# FidoBark.net
KiCad netlist of a schematic drawn in EAGLE
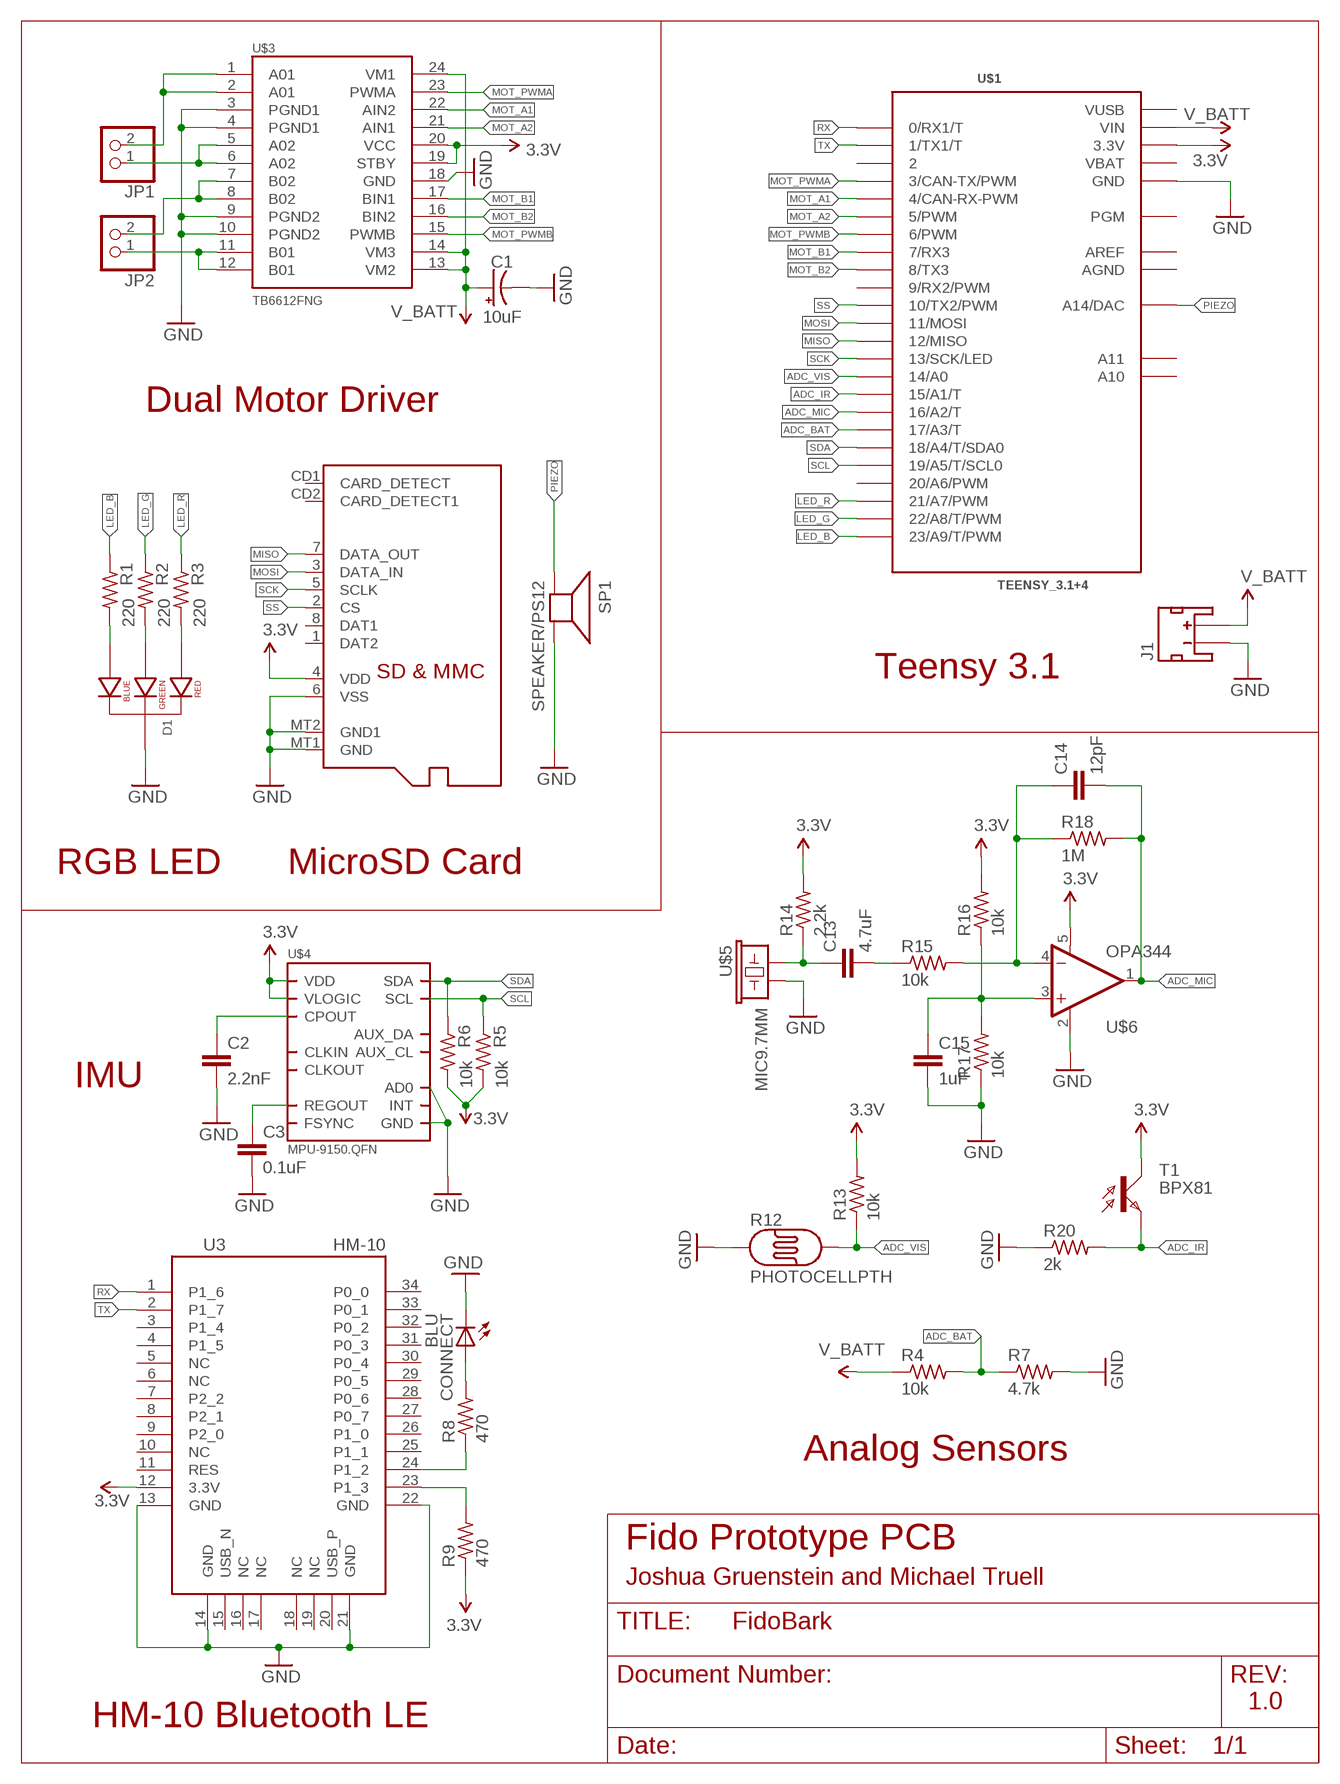
[diagram p0: schematic, sheet 1]

(export (version "E")
  (design (tool "Eeschema 10.0.6"))
  (components
    (comp (ref "C1")
      (value "10uF")
      (footprint "eagle-import:EIA3216")
      (libsource (lib "eagle-import") (part "CAP_POL1206"))
    )
    (comp (ref "C2")
      (value "2.2nF")
      (footprint "eagle-import:C0603")
      (libsource (lib "eagle-import") (part "C-EUC0603"))
    )
    (comp (ref "C3")
      (value "0.1uF")
      (footprint "eagle-import:C0603")
      (libsource (lib "eagle-import") (part "C-EUC0603"))
    )
    (comp (ref "C13")
      (value "4.7uF")
      (footprint "eagle-import:0603-CAP")
      (libsource (lib "eagle-import") (part "CAP0603-CAP"))
    )
    (comp (ref "C14")
      (value "12pF")
      (footprint "eagle-import:0603-CAP")
      (libsource (lib "eagle-import") (part "CAP0603-CAP"))
    )
    (comp (ref "C15")
      (value "1uF")
      (footprint "eagle-import:0603-CAP")
      (libsource (lib "eagle-import") (part "CAP0603-CAP"))
    )
    (comp (ref "CONNECT")
      (value "BLU")
      (footprint "eagle-import:CHIPLED_0805")
      (libsource (lib "eagle-import") (part "LEDCHIPLED_0805"))
    )
    (comp (ref "D1")
      (value "LED-RGB-CC-THRUCLEAR")
      (footprint "eagle-import:LED-RGB-THRU")
      (libsource (lib "eagle-import") (part "LED-RGB-CC-THRUCLEAR"))
    )
    (comp (ref "J1")
      (value "JST_2MM_MALE")
      (footprint "eagle-import:JST-2-SMD")
      (libsource (lib "eagle-import") (part "JST_2MM_MALE"))
    )
    (comp (ref "JP1")
      (value "PINHD-1X2")
      (footprint "eagle-import:1X02")
      (libsource (lib "eagle-import") (part "PINHD-1X2"))
    )
    (comp (ref "JP2")
      (value "PINHD-1X2")
      (footprint "eagle-import:1X02")
      (libsource (lib "eagle-import") (part "PINHD-1X2"))
    )
    (comp (ref "R1")
      (value "220")
      (footprint "eagle-import:R0603")
      (libsource (lib "eagle-import") (part "rcl_R-US_R0603"))
    )
    (comp (ref "R2")
      (value "220")
      (footprint "eagle-import:R0603")
      (libsource (lib "eagle-import") (part "rcl_R-US_R0603"))
    )
    (comp (ref "R3")
      (value "220")
      (footprint "eagle-import:R0603")
      (libsource (lib "eagle-import") (part "rcl_R-US_R0603"))
    )
    (comp (ref "R4")
      (value "10k")
      (footprint "eagle-import:R0603")
      (libsource (lib "eagle-import") (part "rcl_R-US_R0603"))
    )
    (comp (ref "R5")
      (value "10k")
      (footprint "eagle-import:R0603")
      (libsource (lib "eagle-import") (part "rcl_R-US_R0603"))
    )
    (comp (ref "R6")
      (value "10k")
      (footprint "eagle-import:R0603")
      (libsource (lib "eagle-import") (part "rcl_R-US_R0603"))
    )
    (comp (ref "R7")
      (value "4.7k")
      (footprint "eagle-import:R0603")
      (libsource (lib "eagle-import") (part "rcl_R-US_R0603"))
    )
    (comp (ref "R8")
      (value "470")
      (footprint "eagle-import:R0603")
      (libsource (lib "eagle-import") (part "R-US_R0603"))
    )
    (comp (ref "R9")
      (value "470")
      (footprint "eagle-import:R0603")
      (libsource (lib "eagle-import") (part "R-US_R0603"))
    )
    (comp (ref "R12")
      (value "PHOTOCELLPTH")
      (footprint "eagle-import:PHOTOCELL")
      (libsource (lib "eagle-import") (part "PHOTOCELLPTH"))
    )
    (comp (ref "R13")
      (value "10k")
      (footprint "eagle-import:R0603")
      (libsource (lib "eagle-import") (part "R-US_R0603"))
    )
    (comp (ref "R14")
      (value "2.2k")
      (footprint "eagle-import:R0603")
      (libsource (lib "eagle-import") (part "R-US_R0603"))
    )
    (comp (ref "R15")
      (value "10k")
      (footprint "eagle-import:R0603")
      (libsource (lib "eagle-import") (part "R-US_R0603"))
    )
    (comp (ref "R16")
      (value "10k")
      (footprint "eagle-import:R0603")
      (libsource (lib "eagle-import") (part "R-US_R0603"))
    )
    (comp (ref "R17")
      (value "10k")
      (footprint "eagle-import:R0603")
      (libsource (lib "eagle-import") (part "R-US_R0603"))
    )
    (comp (ref "R18")
      (value "1M")
      (footprint "eagle-import:R0603")
      (libsource (lib "eagle-import") (part "R-US_R0603"))
    )
    (comp (ref "R20")
      (value "2k")
      (footprint "eagle-import:R0603")
      (libsource (lib "eagle-import") (part "R-US_R0603"))
    )
    (comp (ref "SP1")
      (value "SPEAKER/PS12")
      (footprint "eagle-import:PS12")
      (libsource (lib "eagle-import") (part "SPEAKER/PS12"))
    )
    (comp (ref "T1")
      (value "BPX81")
      (footprint "eagle-import:BPX81")
      (libsource (lib "eagle-import") (part "BPX81"))
    )
    (comp (ref "U$1")
      (value "TEENSY_3.1+4")
      (footprint "eagle-import:TEENSY_3.1+4")
      (libsource (lib "eagle-import") (part "TEENSY_3.1+4"))
    )
    (comp (ref "U$2")
      (value "MICROSD")
      (footprint "eagle-import:MICROSD")
      (libsource (lib "eagle-import") (part "MICROSD"))
    )
    (comp (ref "U$3")
      (value "TB6612FNG")
      (footprint "eagle-import:SSOP24")
      (libsource (lib "eagle-import") (part "TB6612FNG"))
    )
    (comp (ref "U$4")
      (value "MPU-9150.QFN")
      (footprint "eagle-import:QFN.24.4X4")
      (libsource (lib "eagle-import") (part "MPU-9150.QFN"))
    )
    (comp (ref "U$5")
      (value "MIC9.7MM")
      (footprint "eagle-import:MIC-9.7MM")
      (libsource (lib "eagle-import") (part "MIC9.7MM"))
    )
    (comp (ref "U$6")
      (value "OPA344")
      (footprint "eagle-import:SOT23-5")
      (libsource (lib "eagle-import") (part "OPA344"))
    )
    (comp (ref "U3")
      (value "HM-10")
      (footprint "eagle-import:HM-10")
      (libsource (lib "eagle-import") (part "HM-10"))
    )
  )
  (nets
    (net (code "1") (name "/AGND") (class "Default")
      (node (ref "U$1") (pin "AGND") (pinfunction "AGND_AGND") (pintype "power_in"))
    )
    (net (code "2") (name "/AREF") (class "Default")
      (node (ref "U$1") (pin "AREF") (pinfunction "AREF_AREF") (pintype "power_in"))
    )
    (net (code "3") (name "/VBAT") (class "Default")
      (node (ref "U$1") (pin "VBAT") (pinfunction "VBAT_VBAT") (pintype "power_in"))
    )
    (net (code "4") (name "/VUSB") (class "Default")
      (node (ref "U$1") (pin "VUSB") (pinfunction "VUSB_VUSB") (pintype "power_in"))
    )
    (net (code "5") (name "3.3V") (class "Default")
      (node (ref "R13") (pin "2") (pinfunction "2_2") (pintype "passive"))
      (node (ref "R14") (pin "2") (pinfunction "2_2") (pintype "passive"))
      (node (ref "R16") (pin "2") (pinfunction "2_2") (pintype "passive"))
      (node (ref "R5") (pin "2") (pinfunction "2_2") (pintype "passive"))
      (node (ref "R6") (pin "2") (pinfunction "2_2") (pintype "passive"))
      (node (ref "R9") (pin "1") (pinfunction "1_1") (pintype "passive"))
      (node (ref "T1") (pin "C") (pinfunction "C_C") (pintype "passive"))
      (node (ref "U$1") (pin "3.3V") (pinfunction "3.3V_3.3V") (pintype "power_in"))
      (node (ref "U$1") (pin "3.3V1") (pinfunction "3.3V_3.3V1") (pintype "power_in"))
      (node (ref "U$2") (pin "4") (pinfunction "VDD_4") (pintype "power_in"))
      (node (ref "U$3") (pin "19") (pinfunction "STBY_19") (pintype "bidirectional"))
      (node (ref "U$3") (pin "20") (pinfunction "VCC_20") (pintype "bidirectional"))
      (node (ref "U$4") (pin "13") (pinfunction "VDD_13") (pintype "bidirectional"))
      (node (ref "U$4") (pin "3") (pinfunction "VDD_3") (pintype "bidirectional"))
      (node (ref "U$4") (pin "8") (pinfunction "VLOGIC_8") (pintype "bidirectional"))
      (node (ref "U$6") (pin "5") (pinfunction "V+_5") (pintype "power_in"))
      (node (ref "U3") (pin "12") (pinfunction "3.3V_12") (pintype "bidirectional"))
    )
    (net (code "6") (name "ADC_BAT") (class "Default")
      (node (ref "R4") (pin "2") (pinfunction "2_2") (pintype "passive"))
      (node (ref "R7") (pin "1") (pinfunction "1_1") (pintype "passive"))
      (node (ref "U$1") (pin "17/A3") (pinfunction "17/A3/T_17/A3") (pintype "bidirectional"))
    )
    (net (code "7") (name "ADC_IR") (class "Default")
      (node (ref "R20") (pin "2") (pinfunction "2_2") (pintype "passive"))
      (node (ref "T1") (pin "E") (pinfunction "E_E") (pintype "passive"))
      (node (ref "U$1") (pin "15/A1") (pinfunction "15/A1/T_15/A1") (pintype "bidirectional"))
    )
    (net (code "8") (name "ADC_MIC") (class "Default")
      (node (ref "C14") (pin "2") (pinfunction "2_2") (pintype "passive"))
      (node (ref "R18") (pin "2") (pinfunction "2_2") (pintype "passive"))
      (node (ref "U$1") (pin "16/A2") (pinfunction "16/A2/T_16/A2") (pintype "bidirectional"))
      (node (ref "U$6") (pin "1") (pinfunction "OUT_1") (pintype "output"))
    )
    (net (code "9") (name "ADC_VIS") (class "Default")
      (node (ref "R12") (pin "2") (pinfunction "P$2_2") (pintype "bidirectional"))
      (node (ref "R13") (pin "1") (pinfunction "1_1") (pintype "passive"))
      (node (ref "U$1") (pin "14/A0") (pinfunction "14/A0_14/A0") (pintype "bidirectional"))
    )
    (net (code "10") (name "GND") (class "Default")
      (node (ref "C1") (pin "C") (pinfunction "-_C") (pintype "passive"))
      (node (ref "C15") (pin "2") (pinfunction "2_2") (pintype "passive"))
      (node (ref "C2") (pin "2") (pinfunction "2_2") (pintype "passive"))
      (node (ref "C3") (pin "2") (pinfunction "2_2") (pintype "passive"))
      (node (ref "CONNECT") (pin "C") (pinfunction "C_C") (pintype "passive"))
      (node (ref "D1") (pin "2") (pinfunction "CATHODE_2") (pintype "bidirectional"))
      (node (ref "J1") (pin "1") (pinfunction "-_1") (pintype "bidirectional"))
      (node (ref "R12") (pin "1") (pinfunction "P$1_1") (pintype "bidirectional"))
      (node (ref "R17") (pin "1") (pinfunction "1_1") (pintype "passive"))
      (node (ref "R20") (pin "1") (pinfunction "1_1") (pintype "passive"))
      (node (ref "R7") (pin "2") (pinfunction "2_2") (pintype "passive"))
      (node (ref "SP1") (pin "P$2") (pinfunction "-_P$2") (pintype "passive"))
      (node (ref "U$1") (pin "GND") (pinfunction "GND_GND") (pintype "power_in"))
      (node (ref "U$1") (pin "GND1") (pinfunction "GND_GND1") (pintype "power_in"))
      (node (ref "U$2") (pin "6") (pinfunction "VSS_6") (pintype "power_in"))
      (node (ref "U$2") (pin "MT1") (pinfunction "GND_MT1") (pintype "power_in"))
      (node (ref "U$2") (pin "MT2") (pinfunction "GND1_MT2") (pintype "power_in"))
      (node (ref "U$3") (pin "10") (pinfunction "PGND2_10") (pintype "bidirectional"))
      (node (ref "U$3") (pin "18") (pinfunction "GND_18") (pintype "bidirectional"))
      (node (ref "U$3") (pin "3") (pinfunction "PGND1_3") (pintype "bidirectional"))
      (node (ref "U$3") (pin "4") (pinfunction "PGND1_4") (pintype "bidirectional"))
      (node (ref "U$3") (pin "9") (pinfunction "PGND2_9") (pintype "bidirectional"))
      (node (ref "U$4") (pin "15") (pinfunction "GND_15") (pintype "bidirectional"))
      (node (ref "U$4") (pin "17") (pinfunction "GND_17") (pintype "bidirectional"))
      (node (ref "U$4") (pin "18") (pinfunction "GND_18") (pintype "bidirectional"))
      (node (ref "U$4") (pin "9") (pinfunction "AD0_9") (pintype "bidirectional"))
      (node (ref "U$5") (pin "2") (pinfunction "2_2") (pintype "passive"))
      (node (ref "U$6") (pin "2") (pinfunction "V-_2") (pintype "power_in"))
      (node (ref "U3") (pin "13") (pinfunction "GND_13") (pintype "bidirectional"))
      (node (ref "U3") (pin "14") (pinfunction "GND_14") (pintype "bidirectional"))
      (node (ref "U3") (pin "21") (pinfunction "GND_21") (pintype "bidirectional"))
      (node (ref "U3") (pin "22") (pinfunction "GND_22") (pintype "bidirectional"))
    )
    (net (code "11") (name "LED_B") (class "Default")
      (node (ref "R1") (pin "1") (pinfunction "1_1") (pintype "passive"))
      (node (ref "U$1") (pin "23/A9") (pinfunction "23/A9/T/PWM_23/A9") (pintype "bidirectional"))
    )
    (net (code "12") (name "LED_G") (class "Default")
      (node (ref "R2") (pin "1") (pinfunction "1_1") (pintype "passive"))
      (node (ref "U$1") (pin "22/A8") (pinfunction "22/A8/T/PWM_22/A8") (pintype "bidirectional"))
    )
    (net (code "13") (name "LED_R") (class "Default")
      (node (ref "R3") (pin "1") (pinfunction "1_1") (pintype "passive"))
      (node (ref "U$1") (pin "21/A7") (pinfunction "21/A7/PWM_21/A7") (pintype "bidirectional"))
    )
    (net (code "14") (name "MISO") (class "Default")
      (node (ref "U$1") (pin "12") (pinfunction "12/MISO_12") (pintype "bidirectional"))
      (node (ref "U$2") (pin "7") (pinfunction "DATA_OUT_7") (pintype "output"))
    )
    (net (code "15") (name "MOSI") (class "Default")
      (node (ref "U$1") (pin "11") (pinfunction "11/MOSI_11") (pintype "bidirectional"))
      (node (ref "U$2") (pin "3") (pinfunction "DATA_IN_3") (pintype "input"))
    )
    (net (code "16") (name "MOT_A1") (class "Default")
      (node (ref "U$1") (pin "4") (pinfunction "4/CAN-RX-PWM_4") (pintype "bidirectional"))
      (node (ref "U$3") (pin "22") (pinfunction "AIN2_22") (pintype "bidirectional"))
    )
    (net (code "17") (name "MOT_A2") (class "Default")
      (node (ref "U$1") (pin "5") (pinfunction "5/PWM_5") (pintype "bidirectional"))
      (node (ref "U$3") (pin "21") (pinfunction "AIN1_21") (pintype "bidirectional"))
    )
    (net (code "18") (name "MOT_B1") (class "Default")
      (node (ref "U$1") (pin "7") (pinfunction "7/RX3_7") (pintype "bidirectional"))
      (node (ref "U$3") (pin "17") (pinfunction "BIN1_17") (pintype "bidirectional"))
    )
    (net (code "19") (name "MOT_B2") (class "Default")
      (node (ref "U$1") (pin "8") (pinfunction "8/TX3_8") (pintype "bidirectional"))
      (node (ref "U$3") (pin "16") (pinfunction "BIN2_16") (pintype "bidirectional"))
    )
    (net (code "20") (name "MOT_PWMA") (class "Default")
      (node (ref "U$1") (pin "3") (pinfunction "3/CAN-TX/PWM_3") (pintype "bidirectional"))
      (node (ref "U$3") (pin "23") (pinfunction "PWMA_23") (pintype "bidirectional"))
    )
    (net (code "21") (name "MOT_PWMB") (class "Default")
      (node (ref "U$1") (pin "6") (pinfunction "6/PWM_6") (pintype "bidirectional"))
      (node (ref "U$3") (pin "15") (pinfunction "PWMB_15") (pintype "bidirectional"))
    )
    (net (code "22") (name "Net-(C13-Pad1)") (class "Default")
      (node (ref "C13") (pin "1") (pinfunction "1_1") (pintype "passive"))
      (node (ref "R14") (pin "1") (pinfunction "1_1") (pintype "passive"))
      (node (ref "U$5") (pin "1") (pinfunction "1_1") (pintype "passive"))
    )
    (net (code "23") (name "Net-(C13-Pad2)") (class "Default")
      (node (ref "C13") (pin "2") (pinfunction "2_2") (pintype "passive"))
      (node (ref "R15") (pin "1") (pinfunction "1_1") (pintype "passive"))
    )
    (net (code "24") (name "Net-(CONNECT-PadA)") (class "Default")
      (node (ref "CONNECT") (pin "A") (pinfunction "A_A") (pintype "passive"))
      (node (ref "R8") (pin "2") (pinfunction "2_2") (pintype "passive"))
    )
    (net (code "25") (name "Net-(D1-BLUE_CATHODE)") (class "Default")
      (node (ref "D1") (pin "4") (pinfunction "BLUE_CATHODE_4") (pintype "bidirectional"))
      (node (ref "R1") (pin "2") (pinfunction "2_2") (pintype "passive"))
    )
    (net (code "26") (name "Net-(D1-GREEN_CATHODE)") (class "Default")
      (node (ref "D1") (pin "3") (pinfunction "GREEN_CATHODE_3") (pintype "bidirectional"))
      (node (ref "R2") (pin "2") (pinfunction "2_2") (pintype "passive"))
    )
    (net (code "27") (name "Net-(D1-RED_CATHODE)") (class "Default")
      (node (ref "D1") (pin "1") (pinfunction "RED_CATHODE_1") (pintype "bidirectional"))
      (node (ref "R3") (pin "2") (pinfunction "2_2") (pintype "passive"))
    )
    (net (code "28") (name "Net-(JP1-Pad1)") (class "Default")
      (node (ref "JP1") (pin "1") (pinfunction "1_1") (pintype "passive"))
      (node (ref "U$3") (pin "5") (pinfunction "A02_5") (pintype "bidirectional"))
      (node (ref "U$3") (pin "6") (pinfunction "A02_6") (pintype "bidirectional"))
    )
    (net (code "29") (name "Net-(JP1-Pad2)") (class "Default")
      (node (ref "JP1") (pin "2") (pinfunction "2_2") (pintype "passive"))
      (node (ref "U$3") (pin "1") (pinfunction "A01_1") (pintype "bidirectional"))
      (node (ref "U$3") (pin "2") (pinfunction "A01_2") (pintype "bidirectional"))
    )
    (net (code "30") (name "Net-(JP2-Pad1)") (class "Default")
      (node (ref "JP2") (pin "1") (pinfunction "1_1") (pintype "passive"))
      (node (ref "U$3") (pin "11") (pinfunction "B01_11") (pintype "bidirectional"))
      (node (ref "U$3") (pin "12") (pinfunction "B01_12") (pintype "bidirectional"))
    )
    (net (code "31") (name "Net-(JP2-Pad2)") (class "Default")
      (node (ref "JP2") (pin "2") (pinfunction "2_2") (pintype "passive"))
      (node (ref "U$3") (pin "7") (pinfunction "B02_7") (pintype "bidirectional"))
      (node (ref "U$3") (pin "8") (pinfunction "B02_8") (pintype "bidirectional"))
    )
    (net (code "32") (name "Net-(U$4-CPOUT)") (class "Default")
      (node (ref "C2") (pin "1") (pinfunction "1_1") (pintype "passive"))
      (node (ref "U$4") (pin "20") (pinfunction "CPOUT_20") (pintype "bidirectional"))
    )
    (net (code "33") (name "Net-(U$4-REGOUT)") (class "Default")
      (node (ref "C3") (pin "1") (pinfunction "1_1") (pintype "passive"))
      (node (ref "U$4") (pin "10") (pinfunction "REGOUT_10") (pintype "bidirectional"))
    )
    (net (code "34") (name "Net-(U$6-+IN)") (class "Default")
      (node (ref "C15") (pin "1") (pinfunction "1_1") (pintype "passive"))
      (node (ref "R16") (pin "1") (pinfunction "1_1") (pintype "passive"))
      (node (ref "R17") (pin "2") (pinfunction "2_2") (pintype "passive"))
      (node (ref "U$6") (pin "3") (pinfunction "+IN_3") (pintype "input"))
    )
    (net (code "35") (name "Net-(U$6--IN)") (class "Default")
      (node (ref "C14") (pin "1") (pinfunction "1_1") (pintype "passive"))
      (node (ref "R15") (pin "2") (pinfunction "2_2") (pintype "passive"))
      (node (ref "R18") (pin "1") (pinfunction "1_1") (pintype "passive"))
      (node (ref "U$6") (pin "4") (pinfunction "-IN_4") (pintype "input"))
    )
    (net (code "36") (name "Net-(U3-P1_2)") (class "Default")
      (node (ref "R8") (pin "1") (pinfunction "1_1") (pintype "passive"))
      (node (ref "U3") (pin "24") (pinfunction "P1_2_24") (pintype "bidirectional"))
    )
    (net (code "37") (name "Net-(U3-P1_3)") (class "Default")
      (node (ref "R9") (pin "2") (pinfunction "2_2") (pintype "passive"))
      (node (ref "U3") (pin "23") (pinfunction "P1_3_23") (pintype "bidirectional"))
    )
    (net (code "38") (name "PIEZO") (class "Default")
      (node (ref "SP1") (pin "P$1") (pinfunction "+_P$1") (pintype "passive"))
      (node (ref "U$1") (pin "A14") (pinfunction "A14/DAC_A14") (pintype "bidirectional"))
    )
    (net (code "39") (name "RX") (class "Default")
      (node (ref "U$1") (pin "0") (pinfunction "0/RX1/T_0") (pintype "bidirectional"))
      (node (ref "U3") (pin "1") (pinfunction "P1_6_1") (pintype "bidirectional"))
    )
    (net (code "40") (name "SCK") (class "Default")
      (node (ref "U$1") (pin "13") (pinfunction "13/SCK/LED_13") (pintype "bidirectional"))
      (node (ref "U$2") (pin "5") (pinfunction "SCLK_5") (pintype "input"))
    )
    (net (code "41") (name "SCL") (class "Default")
      (node (ref "R5") (pin "1") (pinfunction "1_1") (pintype "passive"))
      (node (ref "U$1") (pin "19/A5") (pinfunction "19/A5/T/SCL0_19/A5") (pintype "bidirectional"))
      (node (ref "U$4") (pin "23") (pinfunction "SCL_23") (pintype "bidirectional"))
    )
    (net (code "42") (name "SDA") (class "Default")
      (node (ref "R6") (pin "1") (pinfunction "1_1") (pintype "passive"))
      (node (ref "U$1") (pin "18/A4") (pinfunction "18/A4/T/SDA0_18/A4") (pintype "bidirectional"))
      (node (ref "U$4") (pin "24") (pinfunction "SDA_24") (pintype "bidirectional"))
    )
    (net (code "43") (name "SS") (class "Default")
      (node (ref "U$1") (pin "10") (pinfunction "10/TX2/PWM_10") (pintype "bidirectional"))
      (node (ref "U$2") (pin "2") (pinfunction "CS_2") (pintype "input"))
    )
    (net (code "44") (name "TX") (class "Default")
      (node (ref "U$1") (pin "1") (pinfunction "1/TX1/T_1") (pintype "bidirectional"))
      (node (ref "U3") (pin "2") (pinfunction "P1_7_2") (pintype "bidirectional"))
    )
    (net (code "45") (name "V_BATT") (class "Default")
      (node (ref "C1") (pin "A") (pinfunction "+_A") (pintype "passive"))
      (node (ref "J1") (pin "2") (pinfunction "+_2") (pintype "bidirectional"))
      (node (ref "R4") (pin "1") (pinfunction "1_1") (pintype "passive"))
      (node (ref "U$1") (pin "VIN") (pinfunction "VIN_VIN") (pintype "power_in"))
      (node (ref "U$3") (pin "13") (pinfunction "VM2_13") (pintype "bidirectional"))
      (node (ref "U$3") (pin "14") (pinfunction "VM3_14") (pintype "bidirectional"))
      (node (ref "U$3") (pin "24") (pinfunction "VM1_24") (pintype "bidirectional"))
    )
    (net (code "46") (name "unconnected-(J1-PAD1-PadNC1)") (class "Default")
      (node (ref "J1") (pin "NC1") (pinfunction "PAD1_NC1") (pintype "bidirectional"))
    )
    (net (code "47") (name "unconnected-(J1-PAD2-PadNC2)") (class "Default")
      (node (ref "J1") (pin "NC2") (pinfunction "PAD2_NC2") (pintype "bidirectional"))
    )
    (net (code "48") (name "unconnected-(U$1-9{slash}RX2{slash}PWM-Pad9)") (class "Default")
      (node (ref "U$1") (pin "9") (pinfunction "9/RX2/PWM_9") (pintype "bidirectional"))
    )
    (net (code "49") (name "unconnected-(U$1-20{slash}A6{slash}PWM-Pad20{slash}A6)") (class "Default")
      (node (ref "U$1") (pin "20/A6") (pinfunction "20/A6/PWM_20/A6") (pintype "bidirectional"))
    )
    (net (code "50") (name "unconnected-(U$1-Pad2)") (class "Default")
      (node (ref "U$1") (pin "2") (pinfunction "2_2") (pintype "bidirectional"))
    )
    (net (code "51") (name "unconnected-(U$1-PadA10)") (class "Default")
      (node (ref "U$1") (pin "A10") (pinfunction "A10_A10") (pintype "bidirectional"))
    )
    (net (code "52") (name "unconnected-(U$1-PadA11)") (class "Default")
      (node (ref "U$1") (pin "A11") (pinfunction "A11_A11") (pintype "bidirectional"))
    )
    (net (code "53") (name "unconnected-(U$1-PadPGM)") (class "Default")
      (node (ref "U$1") (pin "PGM") (pinfunction "PGM_PGM") (pintype "bidirectional"))
    )
    (net (code "54") (name "unconnected-(U$2-CARD_DETECT-PadCD1)") (class "Default")
      (node (ref "U$2") (pin "CD1") (pinfunction "CARD_DETECT_CD1") (pintype "passive"))
    )
    (net (code "55") (name "unconnected-(U$2-CARD_DETECT1-PadCD2)") (class "Default")
      (node (ref "U$2") (pin "CD2") (pinfunction "CARD_DETECT1_CD2") (pintype "passive"))
    )
    (net (code "56") (name "unconnected-(U$2-DAT1-Pad8)") (class "Default")
      (node (ref "U$2") (pin "8") (pinfunction "DAT1_8") (pintype "bidirectional"))
    )
    (net (code "57") (name "unconnected-(U$2-DAT2-Pad1)") (class "Default")
      (node (ref "U$2") (pin "1") (pinfunction "DAT2_1") (pintype "bidirectional"))
    )
    (net (code "58") (name "unconnected-(U$4-AUX_CL-Pad7)") (class "Default")
      (node (ref "U$4") (pin "7") (pinfunction "AUX_CL_7") (pintype "bidirectional"))
    )
    (net (code "59") (name "unconnected-(U$4-AUX_DA-Pad6)") (class "Default")
      (node (ref "U$4") (pin "6") (pinfunction "AUX_DA_6") (pintype "bidirectional"))
    )
    (net (code "60") (name "unconnected-(U$4-CLKIN-Pad1)") (class "Default")
      (node (ref "U$4") (pin "1") (pinfunction "CLKIN_1") (pintype "bidirectional"))
    )
    (net (code "61") (name "unconnected-(U$4-CLKOUT-Pad22)") (class "Default")
      (node (ref "U$4") (pin "22") (pinfunction "CLKOUT_22") (pintype "bidirectional"))
    )
    (net (code "62") (name "unconnected-(U$4-FSYNC-Pad11)") (class "Default")
      (node (ref "U$4") (pin "11") (pinfunction "FSYNC_11") (pintype "bidirectional"))
    )
    (net (code "63") (name "unconnected-(U$4-INT-Pad12)") (class "Default")
      (node (ref "U$4") (pin "12") (pinfunction "INT_12") (pintype "bidirectional"))
    )
    (net (code "64") (name "unconnected-(U3-NC-Pad5)") (class "Default")
      (node (ref "U3") (pin "5") (pinfunction "NC_5") (pintype "bidirectional"))
    )
    (net (code "65") (name "unconnected-(U3-NC-Pad6)") (class "Default")
      (node (ref "U3") (pin "6") (pinfunction "NC_6") (pintype "bidirectional"))
    )
    (net (code "66") (name "unconnected-(U3-NC-Pad10)") (class "Default")
      (node (ref "U3") (pin "10") (pinfunction "NC_10") (pintype "bidirectional"))
    )
    (net (code "67") (name "unconnected-(U3-NC-Pad16)") (class "Default")
      (node (ref "U3") (pin "16") (pinfunction "NC_16") (pintype "bidirectional"))
    )
    (net (code "68") (name "unconnected-(U3-NC-Pad17)") (class "Default")
      (node (ref "U3") (pin "17") (pinfunction "NC_17") (pintype "bidirectional"))
    )
    (net (code "69") (name "unconnected-(U3-NC-Pad18)") (class "Default")
      (node (ref "U3") (pin "18") (pinfunction "NC_18") (pintype "bidirectional"))
    )
    (net (code "70") (name "unconnected-(U3-NC-Pad19)") (class "Default")
      (node (ref "U3") (pin "19") (pinfunction "NC_19") (pintype "bidirectional"))
    )
    (net (code "71") (name "unconnected-(U3-P0_0-Pad34)") (class "Default")
      (node (ref "U3") (pin "34") (pinfunction "P0_0_34") (pintype "bidirectional"))
    )
    (net (code "72") (name "unconnected-(U3-P0_1-Pad33)") (class "Default")
      (node (ref "U3") (pin "33") (pinfunction "P0_1_33") (pintype "bidirectional"))
    )
    (net (code "73") (name "unconnected-(U3-P0_2-Pad32)") (class "Default")
      (node (ref "U3") (pin "32") (pinfunction "P0_2_32") (pintype "bidirectional"))
    )
    (net (code "74") (name "unconnected-(U3-P0_3-Pad31)") (class "Default")
      (node (ref "U3") (pin "31") (pinfunction "P0_3_31") (pintype "bidirectional"))
    )
    (net (code "75") (name "unconnected-(U3-P0_4-Pad30)") (class "Default")
      (node (ref "U3") (pin "30") (pinfunction "P0_4_30") (pintype "bidirectional"))
    )
    (net (code "76") (name "unconnected-(U3-P0_5-Pad29)") (class "Default")
      (node (ref "U3") (pin "29") (pinfunction "P0_5_29") (pintype "bidirectional"))
    )
    (net (code "77") (name "unconnected-(U3-P0_6-Pad28)") (class "Default")
      (node (ref "U3") (pin "28") (pinfunction "P0_6_28") (pintype "bidirectional"))
    )
    (net (code "78") (name "unconnected-(U3-P0_7-Pad27)") (class "Default")
      (node (ref "U3") (pin "27") (pinfunction "P0_7_27") (pintype "bidirectional"))
    )
    (net (code "79") (name "unconnected-(U3-P1_0-Pad26)") (class "Default")
      (node (ref "U3") (pin "26") (pinfunction "P1_0_26") (pintype "bidirectional"))
    )
    (net (code "80") (name "unconnected-(U3-P1_1-Pad25)") (class "Default")
      (node (ref "U3") (pin "25") (pinfunction "P1_1_25") (pintype "bidirectional"))
    )
    (net (code "81") (name "unconnected-(U3-P1_4-Pad3)") (class "Default")
      (node (ref "U3") (pin "3") (pinfunction "P1_4_3") (pintype "bidirectional"))
    )
    (net (code "82") (name "unconnected-(U3-P1_5-Pad4)") (class "Default")
      (node (ref "U3") (pin "4") (pinfunction "P1_5_4") (pintype "bidirectional"))
    )
    (net (code "83") (name "unconnected-(U3-P2_0-Pad9)") (class "Default")
      (node (ref "U3") (pin "9") (pinfunction "P2_0_9") (pintype "bidirectional"))
    )
    (net (code "84") (name "unconnected-(U3-P2_1-Pad8)") (class "Default")
      (node (ref "U3") (pin "8") (pinfunction "P2_1_8") (pintype "bidirectional"))
    )
    (net (code "85") (name "unconnected-(U3-P2_2-Pad7)") (class "Default")
      (node (ref "U3") (pin "7") (pinfunction "P2_2_7") (pintype "bidirectional"))
    )
    (net (code "86") (name "unconnected-(U3-RES-Pad11)") (class "Default")
      (node (ref "U3") (pin "11") (pinfunction "RES_11") (pintype "bidirectional"))
    )
    (net (code "87") (name "unconnected-(U3-USB_N-Pad15)") (class "Default")
      (node (ref "U3") (pin "15") (pinfunction "USB_N_15") (pintype "bidirectional"))
    )
    (net (code "88") (name "unconnected-(U3-USB_P-Pad20)") (class "Default")
      (node (ref "U3") (pin "20") (pinfunction "USB_P_20") (pintype "bidirectional"))
    )
  )
)
